# 03_-_WIFI_-_BLE.net
KiCad netlist of a schematic drawn in Altium Designer
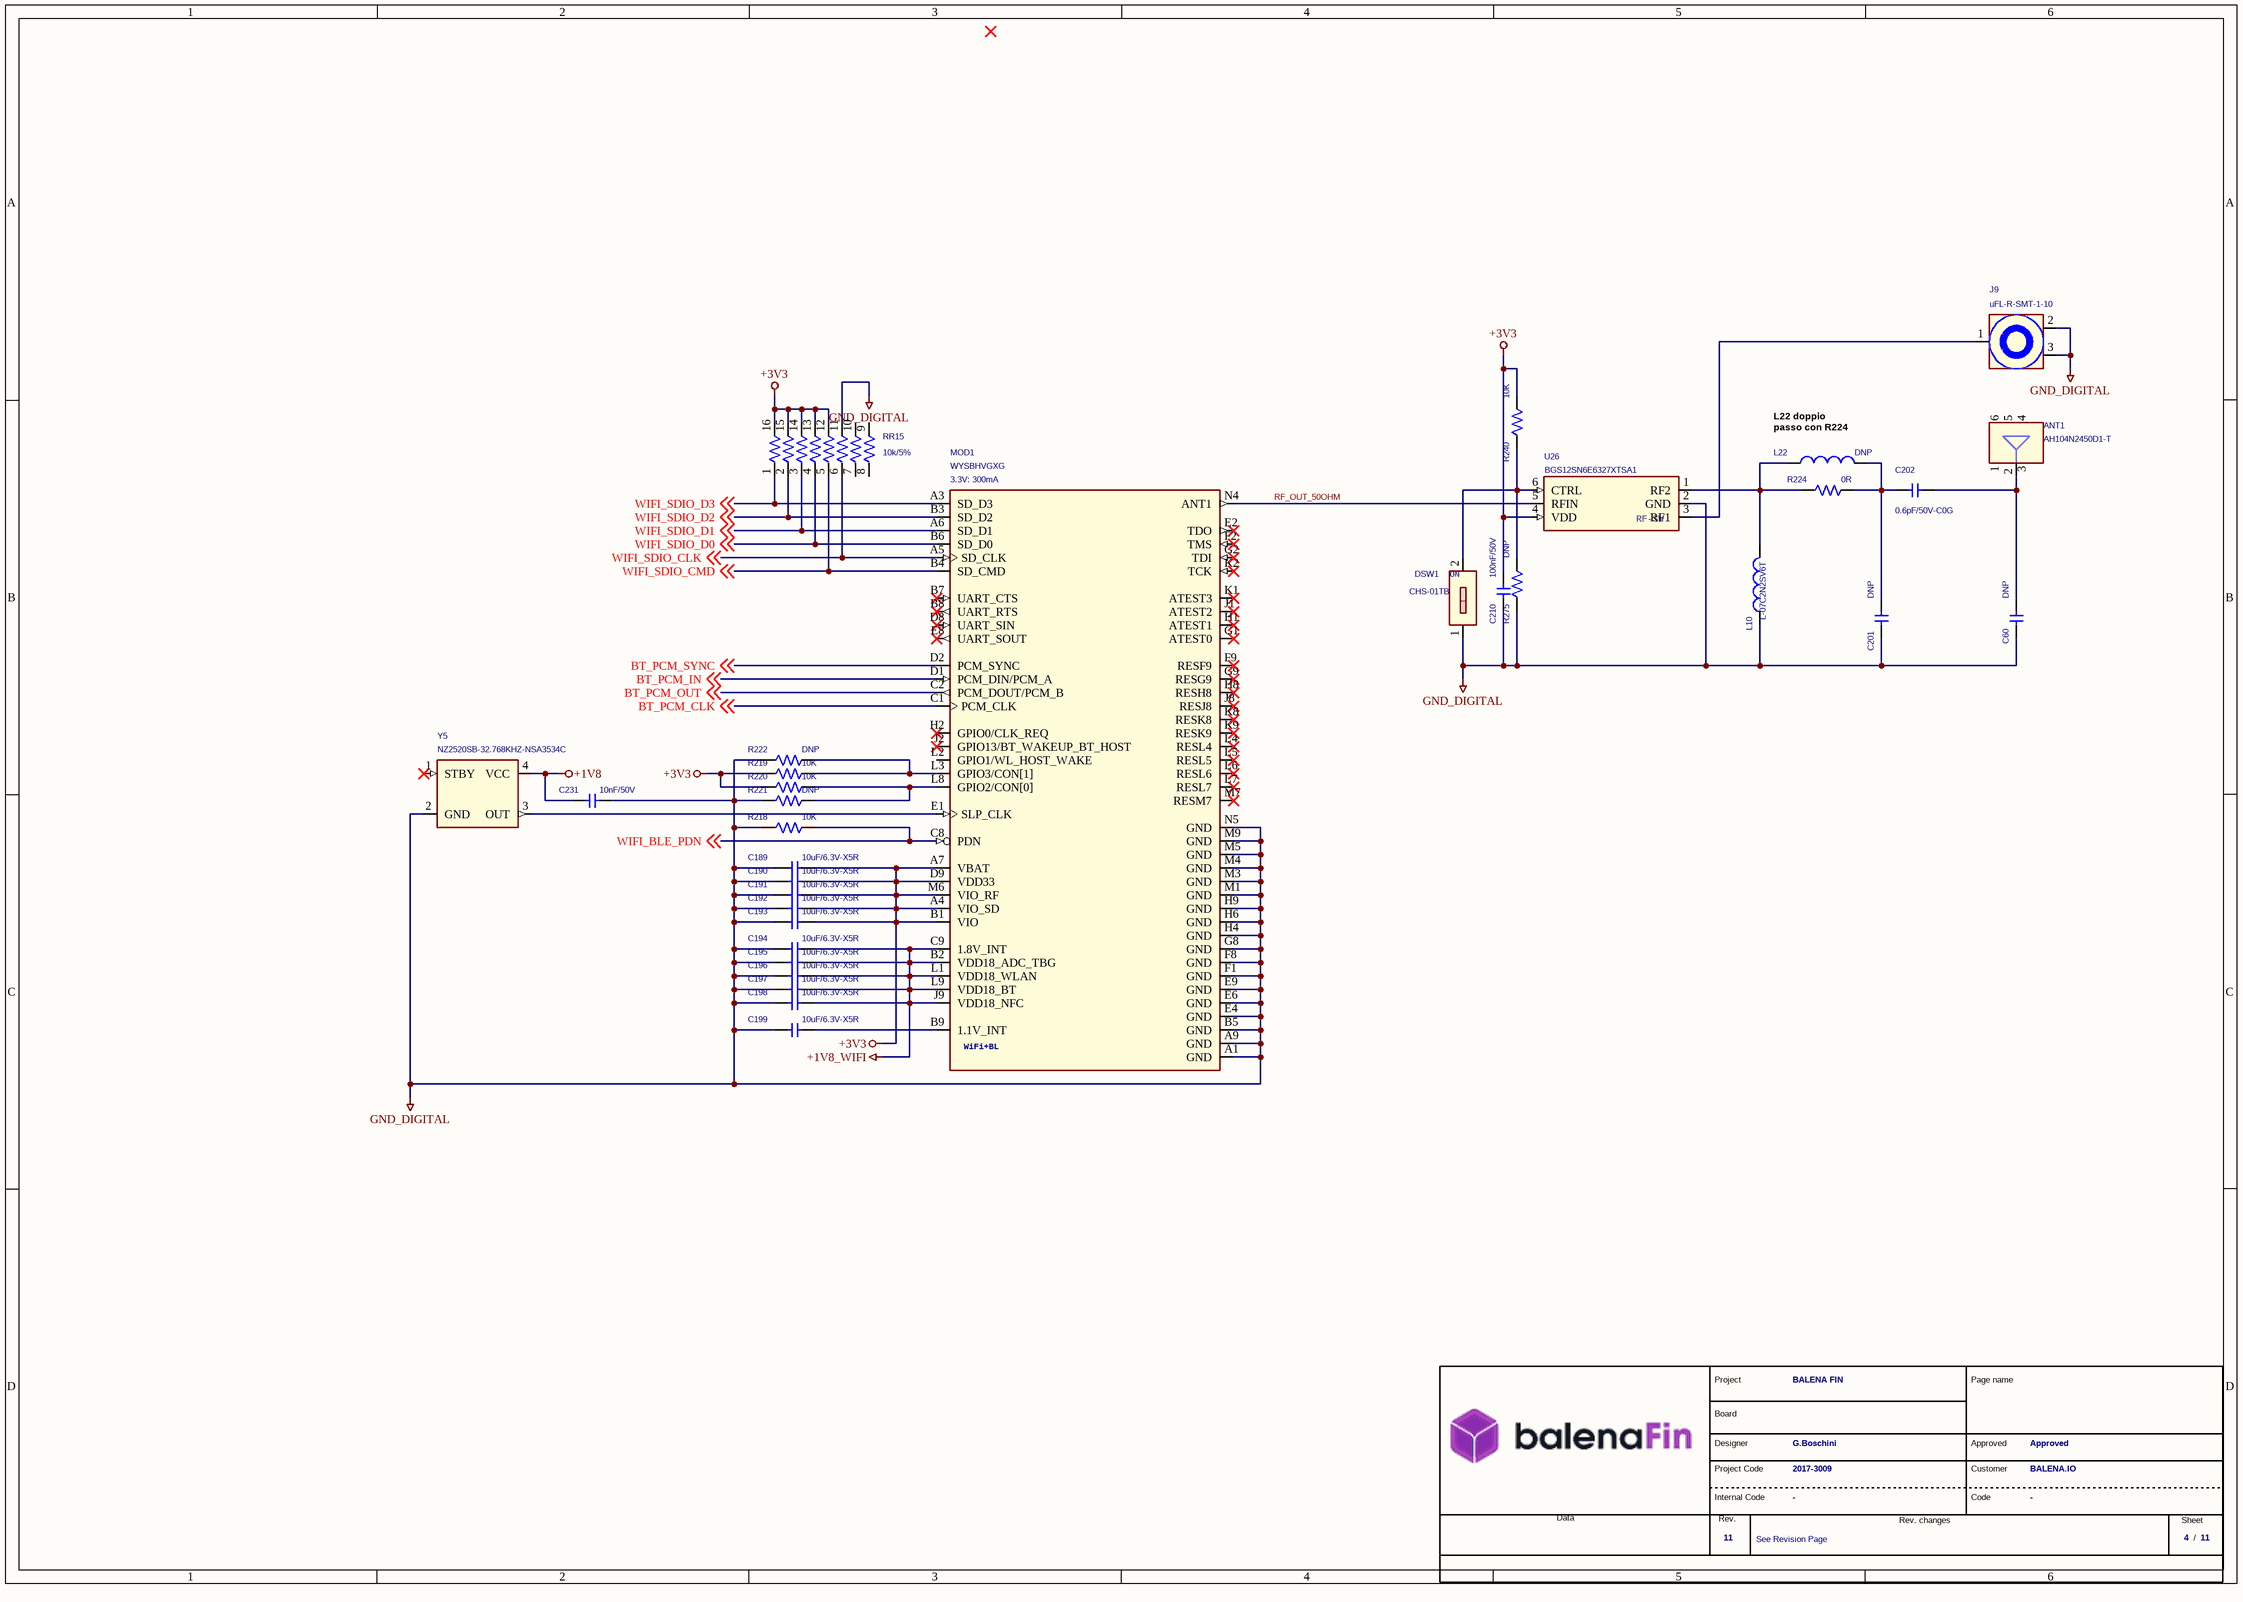
[diagram p0: 03 - WIFI - BLE.SchDoc]

(export (version "E")
  (design (tool "Eeschema 10.0.6"))
  (components
    (comp (ref "ANT1")
      (value "AH104N2450D1-T")
      (footprint "ANT-AH104N")
      (description "2.4GHz, 5.4GHz WLAN Chip RF Antenna 2.4GHz ~ 2.5GHz, 4.9GHz ~ 5.85GHz 2.1dBi,  2.4dBi")
      (libsource (lib "*") (part "ANT - AH104N2450D1-T - 2.4G-5G"))
    )
    (comp (ref "C60")
      (value "DNP")
      (footprint "CS-C-0402")
      (description "CHIP CAP.CER. 0402")
      (fields (field (name "MPN") "Generic"))
      (libsource (lib "*") (part "CS-C-0402"))
    )
    (comp (ref "C189")
      (value "10uF/6.3V-X5R")
      (footprint "CS-C-0402")
      (description "CHIP CAP.CER. 10uF 6.3V 20% X5R 0402")
      (fields (field (name "MPN") "Generic"))
      (libsource (lib "*") (part "CS-C-0402-10u/6V3-X5R"))
    )
    (comp (ref "C190")
      (value "10uF/6.3V-X5R")
      (footprint "CS-C-0402")
      (description "CHIP CAP.CER. 10uF 6.3V 20% X5R 0402")
      (fields (field (name "MPN") "Generic"))
      (libsource (lib "*") (part "CS-C-0402-10u/6V3-X5R"))
    )
    (comp (ref "C191")
      (value "10uF/6.3V-X5R")
      (footprint "CS-C-0402")
      (description "CHIP CAP.CER. 10uF 6.3V 20% X5R 0402")
      (fields (field (name "MPN") "Generic"))
      (libsource (lib "*") (part "CS-C-0402-10u/6V3-X5R"))
    )
    (comp (ref "C192")
      (value "10uF/6.3V-X5R")
      (footprint "CS-C-0402")
      (description "CHIP CAP.CER. 10uF 6.3V 20% X5R 0402")
      (fields (field (name "MPN") "Generic"))
      (libsource (lib "*") (part "CS-C-0402-10u/6V3-X5R"))
    )
    (comp (ref "C193")
      (value "10uF/6.3V-X5R")
      (footprint "CS-C-0402")
      (description "CHIP CAP.CER. 10uF 6.3V 20% X5R 0402")
      (fields (field (name "MPN") "Generic"))
      (libsource (lib "*") (part "CS-C-0402-10u/6V3-X5R"))
    )
    (comp (ref "C194")
      (value "10uF/6.3V-X5R")
      (footprint "CS-C-0402")
      (description "CHIP CAP.CER. 10uF 6.3V 20% X5R 0402")
      (fields (field (name "MPN") "Generic"))
      (libsource (lib "*") (part "CS-C-0402-10u/6V3-X5R"))
    )
    (comp (ref "C195")
      (value "10uF/6.3V-X5R")
      (footprint "CS-C-0402")
      (description "CHIP CAP.CER. 10uF 6.3V 20% X5R 0402")
      (fields (field (name "MPN") "Generic"))
      (libsource (lib "*") (part "CS-C-0402-10u/6V3-X5R"))
    )
    (comp (ref "C196")
      (value "10uF/6.3V-X5R")
      (footprint "CS-C-0402")
      (description "CHIP CAP.CER. 10uF 6.3V 20% X5R 0402")
      (fields (field (name "MPN") "Generic"))
      (libsource (lib "*") (part "CS-C-0402-10u/6V3-X5R"))
    )
    (comp (ref "C197")
      (value "10uF/6.3V-X5R")
      (footprint "CS-C-0402")
      (description "CHIP CAP.CER. 10uF 6.3V 20% X5R 0402")
      (fields (field (name "MPN") "Generic"))
      (libsource (lib "*") (part "CS-C-0402-10u/6V3-X5R"))
    )
    (comp (ref "C198")
      (value "10uF/6.3V-X5R")
      (footprint "CS-C-0402")
      (description "CHIP CAP.CER. 10uF 6.3V 20% X5R 0402")
      (fields (field (name "MPN") "Generic"))
      (libsource (lib "*") (part "CS-C-0402-10u/6V3-X5R"))
    )
    (comp (ref "C199")
      (value "10uF/6.3V-X5R")
      (footprint "CS-C-0402")
      (description "CHIP CAP.CER. 10uF 6.3V 20% X5R 0402")
      (fields (field (name "MPN") "Generic"))
      (libsource (lib "*") (part "CS-C-0402-10u/6V3-X5R"))
    )
    (comp (ref "C201")
      (value "DNP")
      (footprint "CS-C-0402")
      (description "CHIP CAP.CER. 0402")
      (fields (field (name "MPN") "Generic"))
      (libsource (lib "*") (part "CS-C-0402"))
    )
    (comp (ref "C202")
      (value "0.6pF/50V-C0G")
      (footprint "CS-C-0402")
      (description "CHIP CAP.CER. 0.6pF 50V ±0.1pF C0G 0402")
      (fields (field (name "MPN") "Generic"))
      (libsource (lib "*") (part "CS-C-0402-0.6p/50V-C0G"))
    )
    (comp (ref "C210")
      (value "100nF/50V")
      (footprint "CS-C-0402")
      (description "CHIP CAP.CER. 100nF 16V 10% X7R 0402")
      (fields (field (name "MPN") "Generic"))
      (libsource (lib "*") (part "CS-C-0402-100n/16V"))
    )
    (comp (ref "C231")
      (value "10nF/50V")
      (footprint "CS-C-0402")
      (description "CHIP CAP.CER. 10nF 50V 10% X7R 0402")
      (fields (field (name "MPN") "Generic"))
      (libsource (lib "*") (part "CS-C-0402-10n/50V"))
    )
    (comp (ref "DSW1")
      (value "CHS-01TB")
      (footprint "DSS-CHS-01TB")
      (description "Dip Switch SPST 1 Position - Surface Mount Slide (Standard) - Actuator 100mA 6VDC")
      (libsource (lib "*") (part "DIP-SW-1x-CHS-01TB-SMD"))
    )
    (comp (ref "J9")
      (value "uFL-R-SMT-1-10")
      (footprint "J-3-MDS-UFL")
      (description "CONN. RF M U.FL-R-SMT-1(10) HIROSE SMT")
      (libsource (lib "*") (part "UFL - U-FL-R-SMT-1-10"))
    )
    (comp (ref "L10")
      (value "L-07C2N2SV6T")
      (footprint "LS-0402")
      (description "FIXED IND 2.2NH 300MA 160MOHM SM")
      (libsource (lib "*") (part "L - L-07C2N2SV6T-2.2n/0.3A"))
    )
    (comp (ref "L22")
      (value "DNP")
      (footprint "LS-0402")
      (description "FIXED IND 1.8NH 300MA 140MOHM SM")
      (fields (field (name "MPN") "Generic"))
      (libsource (lib "*") (part "L - L-07C1N8SV6T-1.8n/0.3A"))
    )
    (comp (ref "MOD1")
      (value "WYSBHVGXG")
      (footprint "MOD-WYSBHVGXG")
      (description "WiFi 802.11a/b/g/n, Bluetooth v4.2 Module 2.4GHz, 5GHz")
      (fields (field (name "POWER REQUIREMENTS") "3.3V: 300mA"))
      (libsource (lib "*") (part "WIFI-BLE - WYSBHVGXG"))
    )
    (comp (ref "R218")
      (value "10K")
      (footprint "RS-0402")
      (description "CHIP RES. 10K 0402 1/16W 1%")
      (fields (field (name "MPN") "Generic"))
      (libsource (lib "*") (part "RS-0402-10k"))
    )
    (comp (ref "R219")
      (value "10K")
      (footprint "RS-0402")
      (description "CHIP RES. 10K 0402 1/16W 1%")
      (fields (field (name "MPN") "Generic"))
      (libsource (lib "*") (part "RS-0402-10k"))
    )
    (comp (ref "R220")
      (value "10K")
      (footprint "RS-0402")
      (description "CHIP RES. 10K 0402 1/16W 1%")
      (fields (field (name "MPN") "Generic"))
      (libsource (lib "*") (part "RS-0402-10k"))
    )
    (comp (ref "R221")
      (value "DNP")
      (footprint "RS-0402")
      (description "CHIP RES. 0402")
      (fields (field (name "MPN") "Generic"))
      (libsource (lib "*") (part "RS-0402"))
    )
    (comp (ref "R222")
      (value "DNP")
      (footprint "RS-0402")
      (description "CHIP RES. 0402")
      (fields (field (name "MPN") "Generic"))
      (libsource (lib "*") (part "RS-0402"))
    )
    (comp (ref "R224")
      (value "0R")
      (footprint "RS-0402")
      (description "CHIP RES. 0R 0402 1/16W 1%")
      (fields (field (name "MPN") "Generic"))
      (libsource (lib "*") (part "RS-0402-0r"))
    )
    (comp (ref "R240")
      (value "10K")
      (footprint "RS-0402")
      (description "CHIP RES. 10K 0402 1/16W 1%")
      (fields (field (name "MPN") "Generic"))
      (libsource (lib "*") (part "RS-0402-10k"))
    )
    (comp (ref "R275")
      (value "DNP")
      (footprint "RS-0402")
      (description "CHIP RES. 0402")
      (fields (field (name "MPN") "Generic"))
      (libsource (lib "*") (part "RS-0402"))
    )
    (comp (ref "RR15")
      (value "10k/5%")
      (footprint "RR-8X-1506")
      (description "RES ARRAY 8 RES 10K OHM 1506 5%")
      (fields (field (name "MPN") "Generic"))
      (libsource (lib "*") (part "RR-8X-1506-10k/5%"))
    )
    (comp (ref "U26")
      (value "BGS12SN6E6327XTSA1")
      (footprint "XFDFN6")
      (description "IC RF SWITCH SPDT 6GHZ TSNP6-2")
      (libsource (lib "*") (part "RF-SW - BGS12SN6E6327XTSA1"))
    )
    (comp (ref "Y5")
      (value "NZ2520SB-32.768KHZ-NSA3534C")
      (footprint "Y-NZ2520S")
      (description "32.768kHz XO (Standard) CMOS Oscillator 15pF 1.8V  30ppm 1.8V Standby (Power  Down) 4-SMD, No Lead")
      (libsource (lib "*") (part "OSCILLATORE - NZ2520SB-32.768K"))
    )
  )
  (nets
    (net (code "1") (name "+1V8") (class "Default")
      (node (ref "C231") (pin "1") (pinfunction "1_1") (pintype "passive"))
      (node (ref "Y5") (pin "4") (pinfunction "VCC_4") (pintype "power_in"))
    )
    (net (code "2") (name "+1V8_WIFI") (class "Default")
      (node (ref "C194") (pin "2") (pinfunction "2_2") (pintype "passive"))
      (node (ref "C195") (pin "2") (pinfunction "2_2") (pintype "passive"))
      (node (ref "C196") (pin "2") (pinfunction "2_2") (pintype "passive"))
      (node (ref "C197") (pin "2") (pinfunction "2_2") (pintype "passive"))
      (node (ref "C198") (pin "2") (pinfunction "2_2") (pintype "passive"))
      (node (ref "MOD1") (pin "B2") (pinfunction "VDD18_ADC_TBG_B2") (pintype "power_in"))
      (node (ref "MOD1") (pin "C9") (pinfunction "1.8V_INT_C9") (pintype "power_in"))
      (node (ref "MOD1") (pin "J9") (pinfunction "VDD18_NFC_J9") (pintype "power_in"))
      (node (ref "MOD1") (pin "L1") (pinfunction "VDD18_WLAN_L1") (pintype "power_in"))
      (node (ref "MOD1") (pin "L9") (pinfunction "VDD18_BT_L9") (pintype "power_in"))
    )
    (net (code "3") (name "+3V3") (class "Default")
      (node (ref "C189") (pin "2") (pinfunction "2_2") (pintype "passive"))
      (node (ref "C190") (pin "2") (pinfunction "2_2") (pintype "passive"))
      (node (ref "C191") (pin "2") (pinfunction "2_2") (pintype "passive"))
      (node (ref "C192") (pin "2") (pinfunction "2_2") (pintype "passive"))
      (node (ref "C193") (pin "2") (pinfunction "2_2") (pintype "passive"))
      (node (ref "C210") (pin "2") (pinfunction "2_2") (pintype "passive"))
      (node (ref "MOD1") (pin "A4") (pinfunction "VIO_SD_A4") (pintype "power_in"))
      (node (ref "MOD1") (pin "A7") (pinfunction "VBAT_A7") (pintype "power_in"))
      (node (ref "MOD1") (pin "B1") (pinfunction "VIO_B1") (pintype "power_in"))
      (node (ref "MOD1") (pin "D9") (pinfunction "VDD33_D9") (pintype "power_in"))
      (node (ref "MOD1") (pin "M6") (pinfunction "VIO_RF_M6") (pintype "power_in"))
      (node (ref "R219") (pin "1") (pinfunction "1_1") (pintype "passive"))
      (node (ref "R220") (pin "1") (pinfunction "1_1") (pintype "passive"))
      (node (ref "R240") (pin "2") (pinfunction "2_2") (pintype "passive"))
      (node (ref "RR15") (pin "12") (pinfunction "12_12") (pintype "passive"))
      (node (ref "RR15") (pin "13") (pinfunction "13_13") (pintype "passive"))
      (node (ref "RR15") (pin "14") (pinfunction "14_14") (pintype "passive"))
      (node (ref "RR15") (pin "15") (pinfunction "15_15") (pintype "passive"))
      (node (ref "RR15") (pin "16") (pinfunction "16_16") (pintype "passive"))
      (node (ref "U26") (pin "4") (pinfunction "VDD_4") (pintype "input"))
    )
    (net (code "4") (name "/RF_OUT_50OHM") (class "Default")
      (node (ref "MOD1") (pin "N4") (pinfunction "ANT1_N4") (pintype "output"))
      (node (ref "U26") (pin "5") (pinfunction "RFIN_5") (pintype "bidirectional"))
    )
    (net (code "5") (name "BT_PCM_CLK") (class "Default")
      (node (ref "MOD1") (pin "C1") (pinfunction "PCM_CLK_C1") (pintype "bidirectional"))
    )
    (net (code "6") (name "BT_PCM_IN") (class "Default")
      (node (ref "MOD1") (pin "D1") (pinfunction "PCM_DIN/PCM_A_D1") (pintype "input"))
    )
    (net (code "7") (name "BT_PCM_OUT") (class "Default")
      (node (ref "MOD1") (pin "C2") (pinfunction "PCM_DOUT/PCM_B_C2") (pintype "output"))
    )
    (net (code "8") (name "BT_PCM_SYNC") (class "Default")
      (node (ref "MOD1") (pin "D2") (pinfunction "PCM_SYNC_D2") (pintype "bidirectional"))
    )
    (net (code "9") (name "GND_DIGITAL") (class "Default")
      (node (ref "C189") (pin "1") (pinfunction "1_1") (pintype "passive"))
      (node (ref "C190") (pin "1") (pinfunction "1_1") (pintype "passive"))
      (node (ref "C191") (pin "1") (pinfunction "1_1") (pintype "passive"))
      (node (ref "C192") (pin "1") (pinfunction "1_1") (pintype "passive"))
      (node (ref "C193") (pin "1") (pinfunction "1_1") (pintype "passive"))
      (node (ref "C194") (pin "1") (pinfunction "1_1") (pintype "passive"))
      (node (ref "C195") (pin "1") (pinfunction "1_1") (pintype "passive"))
      (node (ref "C196") (pin "1") (pinfunction "1_1") (pintype "passive"))
      (node (ref "C197") (pin "1") (pinfunction "1_1") (pintype "passive"))
      (node (ref "C198") (pin "1") (pinfunction "1_1") (pintype "passive"))
      (node (ref "C199") (pin "1") (pinfunction "1_1") (pintype "passive"))
      (node (ref "C201") (pin "2") (pinfunction "2_2") (pintype "passive"))
      (node (ref "C210") (pin "1") (pinfunction "1_1") (pintype "passive"))
      (node (ref "C231") (pin "2") (pinfunction "2_2") (pintype "passive"))
      (node (ref "C60") (pin "2") (pinfunction "2_2") (pintype "passive"))
      (node (ref "DSW1") (pin "1") (pinfunction "1_1") (pintype "passive"))
      (node (ref "J9") (pin "2") (pinfunction "2_2") (pintype "passive"))
      (node (ref "J9") (pin "3") (pinfunction "3_3") (pintype "passive"))
      (node (ref "L10") (pin "1") (pinfunction "C_1") (pintype "passive"))
      (node (ref "MOD1") (pin "A1") (pinfunction "GND_A1") (pintype "power_in"))
      (node (ref "MOD1") (pin "A9") (pinfunction "GND_A9") (pintype "power_in"))
      (node (ref "MOD1") (pin "B5") (pinfunction "GND_B5") (pintype "power_in"))
      (node (ref "MOD1") (pin "E4") (pinfunction "GND_E4") (pintype "power_in"))
      (node (ref "MOD1") (pin "E6") (pinfunction "GND_E6") (pintype "power_in"))
      (node (ref "MOD1") (pin "E9") (pinfunction "GND_E9") (pintype "power_in"))
      (node (ref "MOD1") (pin "F1") (pinfunction "GND_F1") (pintype "power_in"))
      (node (ref "MOD1") (pin "F8") (pinfunction "GND_F8") (pintype "power_in"))
      (node (ref "MOD1") (pin "G8") (pinfunction "GND_G8") (pintype "power_in"))
      (node (ref "MOD1") (pin "H4") (pinfunction "GND_H4") (pintype "power_in"))
      (node (ref "MOD1") (pin "H6") (pinfunction "GND_H6") (pintype "power_in"))
      (node (ref "MOD1") (pin "H9") (pinfunction "GND_H9") (pintype "power_in"))
      (node (ref "MOD1") (pin "M1") (pinfunction "GND_M1") (pintype "power_in"))
      (node (ref "MOD1") (pin "M3") (pinfunction "GND_M3") (pintype "power_in"))
      (node (ref "MOD1") (pin "M4") (pinfunction "GND_M4") (pintype "power_in"))
      (node (ref "MOD1") (pin "M5") (pinfunction "GND_M5") (pintype "power_in"))
      (node (ref "MOD1") (pin "M9") (pinfunction "GND_M9") (pintype "power_in"))
      (node (ref "MOD1") (pin "N5") (pinfunction "GND_N5") (pintype "power_in"))
      (node (ref "R218") (pin "1") (pinfunction "1_1") (pintype "passive"))
      (node (ref "R221") (pin "1") (pinfunction "1_1") (pintype "passive"))
      (node (ref "R222") (pin "1") (pinfunction "1_1") (pintype "passive"))
      (node (ref "R275") (pin "1") (pinfunction "1_1") (pintype "passive"))
      (node (ref "RR15") (pin "11") (pinfunction "11_11") (pintype "passive"))
      (node (ref "U26") (pin "2") (pinfunction "GND_2") (pintype "power_in"))
      (node (ref "Y5") (pin "2") (pinfunction "GND_2") (pintype "power_in"))
    )
    (net (code "10") (name "Net-(ANT1-Pad2)") (class "Default")
      (node (ref "ANT1") (pin "2") (pinfunction "2_2") (pintype "passive"))
      (node (ref "C202") (pin "2") (pinfunction "2_2") (pintype "passive"))
      (node (ref "C60") (pin "1") (pinfunction "1_1") (pintype "passive"))
    )
    (net (code "11") (name "Net-(L10-A)") (class "Default")
      (node (ref "L10") (pin "2") (pinfunction "A_2") (pintype "passive"))
      (node (ref "L22") (pin "1") (pinfunction "C_1") (pintype "passive"))
      (node (ref "R224") (pin "1") (pinfunction "1_1") (pintype "passive"))
      (node (ref "U26") (pin "1") (pinfunction "RF2_1") (pintype "bidirectional"))
    )
    (net (code "12") (name "Net-(L22-A)") (class "Default")
      (node (ref "C201") (pin "1") (pinfunction "1_1") (pintype "passive"))
      (node (ref "C202") (pin "1") (pinfunction "1_1") (pintype "passive"))
      (node (ref "L22") (pin "2") (pinfunction "A_2") (pintype "passive"))
      (node (ref "R224") (pin "2") (pinfunction "2_2") (pintype "passive"))
    )
    (net (code "13") (name "Net-(MOD1-1.1V_INT)") (class "Default")
      (node (ref "C199") (pin "2") (pinfunction "2_2") (pintype "passive"))
      (node (ref "MOD1") (pin "B9") (pinfunction "1.1V_INT_B9") (pintype "power_in"))
    )
    (net (code "14") (name "Net-(MOD1-GPIO2{slash}CON[0])") (class "Default")
      (node (ref "MOD1") (pin "L8") (pinfunction "GPIO2/CON[0]_L8") (pintype "passive"))
      (node (ref "R220") (pin "2") (pinfunction "2_2") (pintype "passive"))
      (node (ref "R221") (pin "2") (pinfunction "2_2") (pintype "passive"))
    )
    (net (code "15") (name "Net-(MOD1-GPIO3{slash}CON[1])") (class "Default")
      (node (ref "MOD1") (pin "L3") (pinfunction "GPIO3/CON[1]_L3") (pintype "passive"))
      (node (ref "R219") (pin "2") (pinfunction "2_2") (pintype "passive"))
      (node (ref "R222") (pin "2") (pinfunction "2_2") (pintype "passive"))
    )
    (net (code "16") (name "Net-(MOD1-SLP_CLK)") (class "Default")
      (node (ref "MOD1") (pin "E1") (pinfunction "SLP_CLK_E1") (pintype "input"))
      (node (ref "Y5") (pin "3") (pinfunction "OUT_3") (pintype "output"))
    )
    (net (code "17") (name "Net-(U26-CTRL)") (class "Default")
      (node (ref "DSW1") (pin "2") (pinfunction "2_2") (pintype "passive"))
      (node (ref "R240") (pin "1") (pinfunction "1_1") (pintype "passive"))
      (node (ref "R275") (pin "2") (pinfunction "2_2") (pintype "passive"))
      (node (ref "U26") (pin "6") (pinfunction "CTRL_6") (pintype "input"))
    )
    (net (code "18") (name "Net-(U26-RF1)") (class "Default")
      (node (ref "J9") (pin "1") (pinfunction "1_1") (pintype "passive"))
      (node (ref "U26") (pin "3") (pinfunction "RF1_3") (pintype "bidirectional"))
    )
    (net (code "19") (name "WIFI_BLE_PDN") (class "Default")
      (node (ref "MOD1") (pin "C8") (pinfunction "PDN_C8") (pintype "input"))
      (node (ref "R218") (pin "2") (pinfunction "2_2") (pintype "passive"))
    )
    (net (code "20") (name "WIFI_SDIO_CLK") (class "Default")
      (node (ref "MOD1") (pin "A5") (pinfunction "SD_CLK_A5") (pintype "input"))
      (node (ref "RR15") (pin "6") (pinfunction "6_6") (pintype "passive"))
    )
    (net (code "21") (name "WIFI_SDIO_CMD") (class "Default")
      (node (ref "MOD1") (pin "B4") (pinfunction "SD_CMD_B4") (pintype "bidirectional"))
      (node (ref "RR15") (pin "5") (pinfunction "5_5") (pintype "passive"))
    )
    (net (code "22") (name "WIFI_SDIO_D0") (class "Default")
      (node (ref "MOD1") (pin "B6") (pinfunction "SD_D0_B6") (pintype "bidirectional"))
      (node (ref "RR15") (pin "4") (pinfunction "4_4") (pintype "passive"))
    )
    (net (code "23") (name "WIFI_SDIO_D1") (class "Default")
      (node (ref "MOD1") (pin "A6") (pinfunction "SD_D1_A6") (pintype "bidirectional"))
      (node (ref "RR15") (pin "3") (pinfunction "3_3") (pintype "passive"))
    )
    (net (code "24") (name "WIFI_SDIO_D2") (class "Default")
      (node (ref "MOD1") (pin "B3") (pinfunction "SD_D2_B3") (pintype "bidirectional"))
      (node (ref "RR15") (pin "2") (pinfunction "2_2") (pintype "passive"))
    )
    (net (code "25") (name "WIFI_SDIO_D3") (class "Default")
      (node (ref "MOD1") (pin "A3") (pinfunction "SD_D3_A3") (pintype "bidirectional"))
      (node (ref "RR15") (pin "1") (pinfunction "1_1") (pintype "passive"))
    )
    (net (code "26") (name "unconnected-(ANT1-Pad1)") (class "Default")
      (node (ref "ANT1") (pin "1") (pinfunction "1_1") (pintype "passive"))
    )
    (net (code "27") (name "unconnected-(ANT1-Pad3)") (class "Default")
      (node (ref "ANT1") (pin "3") (pinfunction "3_3") (pintype "passive"))
    )
    (net (code "28") (name "unconnected-(ANT1-Pad4)") (class "Default")
      (node (ref "ANT1") (pin "4") (pinfunction "4_4") (pintype "passive"))
    )
    (net (code "29") (name "unconnected-(ANT1-Pad5)") (class "Default")
      (node (ref "ANT1") (pin "5") (pinfunction "5_5") (pintype "passive"))
    )
    (net (code "30") (name "unconnected-(ANT1-Pad6)") (class "Default")
      (node (ref "ANT1") (pin "6") (pinfunction "6_6") (pintype "passive"))
    )
    (net (code "31") (name "unconnected-(MOD1-ATEST0-PadG1)") (class "Default")
      (node (ref "MOD1") (pin "G1") (pinfunction "ATEST0_G1") (pintype "passive+no_connect"))
    )
    (net (code "32") (name "unconnected-(MOD1-ATEST1-PadH1)") (class "Default")
      (node (ref "MOD1") (pin "H1") (pinfunction "ATEST1_H1") (pintype "passive+no_connect"))
    )
    (net (code "33") (name "unconnected-(MOD1-ATEST2-PadJ1)") (class "Default")
      (node (ref "MOD1") (pin "J1") (pinfunction "ATEST2_J1") (pintype "passive+no_connect"))
    )
    (net (code "34") (name "unconnected-(MOD1-ATEST3-PadK1)") (class "Default")
      (node (ref "MOD1") (pin "K1") (pinfunction "ATEST3_K1") (pintype "passive+no_connect"))
    )
    (net (code "35") (name "unconnected-(MOD1-GPIO0{slash}CLK_REQ-PadH2)") (class "Default")
      (node (ref "MOD1") (pin "H2") (pinfunction "GPIO0/CLK_REQ_H2") (pintype "passive+no_connect"))
    )
    (net (code "36") (name "unconnected-(MOD1-GPIO1{slash}WL_HOST_WAKE-PadL2)") (class "Default")
      (node (ref "MOD1") (pin "L2") (pinfunction "GPIO1/WL_HOST_WAKE_L2") (pintype "passive"))
    )
    (net (code "37") (name "unconnected-(MOD1-GPIO13{slash}BT_WAKEUP_BT_HOST-PadJ2)") (class "Default")
      (node (ref "MOD1") (pin "J2") (pinfunction "GPIO13/BT_WAKEUP_BT_HOST_J2") (pintype "passive+no_connect"))
    )
    (net (code "38") (name "unconnected-(MOD1-RESF9-PadF9)") (class "Default")
      (node (ref "MOD1") (pin "F9") (pinfunction "RESF9_F9") (pintype "passive+no_connect"))
    )
    (net (code "39") (name "unconnected-(MOD1-RESG9-PadG9)") (class "Default")
      (node (ref "MOD1") (pin "G9") (pinfunction "RESG9_G9") (pintype "passive+no_connect"))
    )
    (net (code "40") (name "unconnected-(MOD1-RESH8-PadH8)") (class "Default")
      (node (ref "MOD1") (pin "H8") (pinfunction "RESH8_H8") (pintype "passive+no_connect"))
    )
    (net (code "41") (name "unconnected-(MOD1-RESJ8-PadJ8)") (class "Default")
      (node (ref "MOD1") (pin "J8") (pinfunction "RESJ8_J8") (pintype "passive+no_connect"))
    )
    (net (code "42") (name "unconnected-(MOD1-RESK8-PadK8)") (class "Default")
      (node (ref "MOD1") (pin "K8") (pinfunction "RESK8_K8") (pintype "passive+no_connect"))
    )
    (net (code "43") (name "unconnected-(MOD1-RESK9-PadK9)") (class "Default")
      (node (ref "MOD1") (pin "K9") (pinfunction "RESK9_K9") (pintype "passive+no_connect"))
    )
    (net (code "44") (name "unconnected-(MOD1-RESL4-PadL4)") (class "Default")
      (node (ref "MOD1") (pin "L4") (pinfunction "RESL4_L4") (pintype "passive+no_connect"))
    )
    (net (code "45") (name "unconnected-(MOD1-RESL5-PadL5)") (class "Default")
      (node (ref "MOD1") (pin "L5") (pinfunction "RESL5_L5") (pintype "passive+no_connect"))
    )
    (net (code "46") (name "unconnected-(MOD1-RESL6-PadL6)") (class "Default")
      (node (ref "MOD1") (pin "L6") (pinfunction "RESL6_L6") (pintype "passive+no_connect"))
    )
    (net (code "47") (name "unconnected-(MOD1-RESL7-PadL7)") (class "Default")
      (node (ref "MOD1") (pin "L7") (pinfunction "RESL7_L7") (pintype "passive+no_connect"))
    )
    (net (code "48") (name "unconnected-(MOD1-RESM7-PadM7)") (class "Default")
      (node (ref "MOD1") (pin "M7") (pinfunction "RESM7_M7") (pintype "passive+no_connect"))
    )
    (net (code "49") (name "unconnected-(MOD1-TCK-PadK2)") (class "Default")
      (node (ref "MOD1") (pin "K2") (pinfunction "TCK_K2") (pintype "input+no_connect"))
    )
    (net (code "50") (name "unconnected-(MOD1-TDI-PadG2)") (class "Default")
      (node (ref "MOD1") (pin "G2") (pinfunction "TDI_G2") (pintype "input+no_connect"))
    )
    (net (code "51") (name "unconnected-(MOD1-TDO-PadE2)") (class "Default")
      (node (ref "MOD1") (pin "E2") (pinfunction "TDO_E2") (pintype "output+no_connect"))
    )
    (net (code "52") (name "unconnected-(MOD1-TMS-PadF2)") (class "Default")
      (node (ref "MOD1") (pin "F2") (pinfunction "TMS_F2") (pintype "input+no_connect"))
    )
    (net (code "53") (name "unconnected-(MOD1-UART_CTS-PadB7)") (class "Default")
      (node (ref "MOD1") (pin "B7") (pinfunction "UART_CTS_B7") (pintype "input+no_connect"))
    )
    (net (code "54") (name "unconnected-(MOD1-UART_RTS-PadB8)") (class "Default")
      (node (ref "MOD1") (pin "B8") (pinfunction "UART_RTS_B8") (pintype "output+no_connect"))
    )
    (net (code "55") (name "unconnected-(MOD1-UART_SIN-PadD8)") (class "Default")
      (node (ref "MOD1") (pin "D8") (pinfunction "UART_SIN_D8") (pintype "input+no_connect"))
    )
    (net (code "56") (name "unconnected-(MOD1-UART_SOUT-PadE8)") (class "Default")
      (node (ref "MOD1") (pin "E8") (pinfunction "UART_SOUT_E8") (pintype "output+no_connect"))
    )
    (net (code "57") (name "unconnected-(RR15-Pad7)") (class "Default")
      (node (ref "RR15") (pin "7") (pinfunction "7_7") (pintype "passive"))
    )
    (net (code "58") (name "unconnected-(RR15-Pad8)") (class "Default")
      (node (ref "RR15") (pin "8") (pinfunction "8_8") (pintype "passive"))
    )
    (net (code "59") (name "unconnected-(RR15-Pad9)") (class "Default")
      (node (ref "RR15") (pin "9") (pinfunction "9_9") (pintype "passive"))
    )
    (net (code "60") (name "unconnected-(RR15-Pad10)") (class "Default")
      (node (ref "RR15") (pin "10") (pinfunction "10_10") (pintype "passive"))
    )
    (net (code "61") (name "unconnected-(Y5-STBY-Pad1)") (class "Default")
      (node (ref "Y5") (pin "1") (pinfunction "STBY_1") (pintype "input+no_connect"))
    )
  )
)
